# pecl_sampler_v3.net
KiCad netlist of a schematic drawn in EAGLE
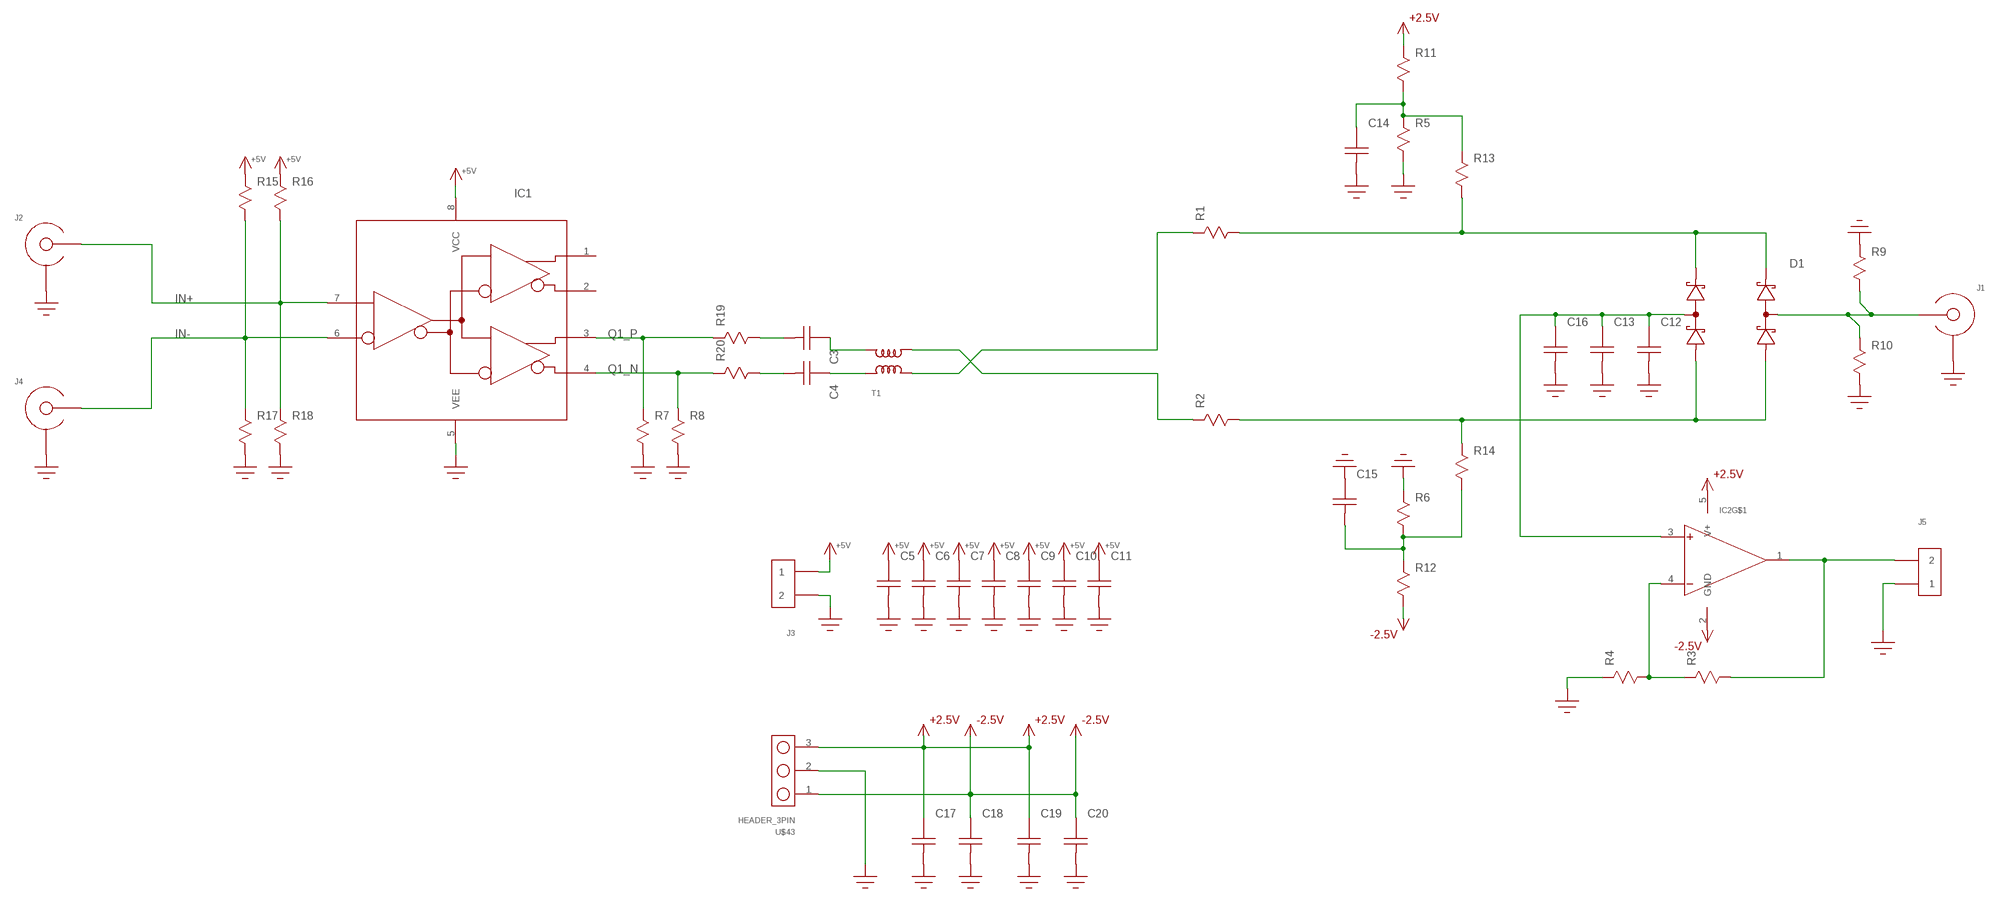
[diagram p0: schematic, sheet 1]

(export (version "E")
  (design (tool "Eeschema 10.0.6"))
  (components
    (comp (ref "C3") (value "C") (footprint "eagle-import:C0402") (libsource (lib "eagle-import") (part "C")))
    (comp (ref "C4") (value "C") (footprint "eagle-import:C0402") (libsource (lib "eagle-import") (part "C")))
    (comp (ref "C5")
      (value "C0603")
      (footprint "eagle-import:C0603")
      (libsource (lib "eagle-import") (part "C0603"))
    )
    (comp (ref "C6")
      (value "C0603")
      (footprint "eagle-import:C0603")
      (libsource (lib "eagle-import") (part "C0603"))
    )
    (comp (ref "C7")
      (value "C0805")
      (footprint "eagle-import:0805")
      (libsource (lib "eagle-import") (part "C0805"))
    )
    (comp (ref "C8")
      (value "C0603")
      (footprint "eagle-import:C0603")
      (libsource (lib "eagle-import") (part "C0603"))
    )
    (comp (ref "C9")
      (value "C0603")
      (footprint "eagle-import:C0603")
      (libsource (lib "eagle-import") (part "C0603"))
    )
    (comp (ref "C10")
      (value "C0603")
      (footprint "eagle-import:C0603")
      (libsource (lib "eagle-import") (part "C0603"))
    )
    (comp (ref "C11")
      (value "C0603")
      (footprint "eagle-import:C0603")
      (libsource (lib "eagle-import") (part "C0603"))
    )
    (comp (ref "C12")
      (value "C")
      (footprint "eagle-import:C0402")
      (libsource (lib "eagle-import") (part "C"))
    )
    (comp (ref "C13")
      (value "C")
      (footprint "eagle-import:C0402")
      (libsource (lib "eagle-import") (part "C"))
    )
    (comp (ref "C14")
      (value "C")
      (footprint "eagle-import:C0402")
      (libsource (lib "eagle-import") (part "C"))
    )
    (comp (ref "C15")
      (value "C")
      (footprint "eagle-import:C0402")
      (libsource (lib "eagle-import") (part "C"))
    )
    (comp (ref "C16")
      (value "C")
      (footprint "eagle-import:C0402")
      (libsource (lib "eagle-import") (part "C"))
    )
    (comp (ref "C17")
      (value "C0603")
      (footprint "eagle-import:C0603")
      (libsource (lib "eagle-import") (part "C0603"))
    )
    (comp (ref "C18")
      (value "C0603")
      (footprint "eagle-import:C0603")
      (libsource (lib "eagle-import") (part "C0603"))
    )
    (comp (ref "C19")
      (value "C0603")
      (footprint "eagle-import:C0603")
      (libsource (lib "eagle-import") (part "C0603"))
    )
    (comp (ref "C20")
      (value "C0603")
      (footprint "eagle-import:C0603")
      (libsource (lib "eagle-import") (part "C0603"))
    )
    (comp (ref "D1")
      (value "SMS3923-081")
      (footprint "eagle-import:SC-88")
      (libsource (lib "eagle-import") (part "SMS3923-081"))
    )
    (comp (ref "IC1")
      (value "SY10EP89V")
      (footprint "eagle-import:SOIC8")
      (libsource (lib "eagle-import") (part "SY10EP89V"))
    )
    (comp (ref "IC2")
      (value "MCP6V81")
      (footprint "eagle-import:SOT23-5")
      (libsource (lib "eagle-import") (part "MCP6V81"))
    )
    (comp (ref "J1")
      (value "SMA-EDGE-LAUNCH4L-4020-TAPER-FIXED")
      (footprint "eagle-import:SMA_EDGE_LAUNCH_4L_4020_TAPER_FIXED")
      (libsource (lib "eagle-import") (part "SMA-EDGE-LAUNCH4L-4020-TAPER-FIXED"))
    )
    (comp (ref "J2")
      (value "SMA-EDGE-LAUNCH4L-4020-TAPER-FIXED")
      (footprint "eagle-import:SMA_EDGE_LAUNCH_4L_4020_TAPER_FIXED")
      (libsource (lib "eagle-import") (part "SMA-EDGE-LAUNCH4L-4020-TAPER-FIXED"))
    )
    (comp (ref "J3")
      (value "HEADER_2PIN")
      (footprint "eagle-import:HEADER_2PIN")
      (libsource (lib "eagle-import") (part "HEADER_2PIN"))
    )
    (comp (ref "J4")
      (value "SMA-EDGE-LAUNCH4L-4020-TAPER-FIXED")
      (footprint "eagle-import:SMA_EDGE_LAUNCH_4L_4020_TAPER_FIXED")
      (libsource (lib "eagle-import") (part "SMA-EDGE-LAUNCH4L-4020-TAPER-FIXED"))
    )
    (comp (ref "J5")
      (value "HEADER_2PIN")
      (footprint "eagle-import:HEADER_2PIN")
      (libsource (lib "eagle-import") (part "HEADER_2PIN"))
    )
    (comp (ref "R1")
      (value "R0402")
      (footprint "eagle-import:0402")
      (libsource (lib "eagle-import") (part "R0402"))
    )
    (comp (ref "R2")
      (value "R0402")
      (footprint "eagle-import:0402")
      (libsource (lib "eagle-import") (part "R0402"))
    )
    (comp (ref "R3")
      (value "R0603")
      (footprint "eagle-import:R0603")
      (libsource (lib "eagle-import") (part "R0603"))
    )
    (comp (ref "R4")
      (value "R0603")
      (footprint "eagle-import:R0603")
      (libsource (lib "eagle-import") (part "R0603"))
    )
    (comp (ref "R5")
      (value "R0603")
      (footprint "eagle-import:R0603")
      (libsource (lib "eagle-import") (part "R0603"))
    )
    (comp (ref "R6")
      (value "R0603")
      (footprint "eagle-import:R0603")
      (libsource (lib "eagle-import") (part "R0603"))
    )
    (comp (ref "R7")
      (value "R0603")
      (footprint "eagle-import:R0603")
      (libsource (lib "eagle-import") (part "R0603"))
    )
    (comp (ref "R8")
      (value "R0603")
      (footprint "eagle-import:R0603")
      (libsource (lib "eagle-import") (part "R0603"))
    )
    (comp (ref "R9")
      (value "R0402")
      (footprint "eagle-import:0402")
      (libsource (lib "eagle-import") (part "R0402"))
    )
    (comp (ref "R10")
      (value "R0402")
      (footprint "eagle-import:0402")
      (libsource (lib "eagle-import") (part "R0402"))
    )
    (comp (ref "R11")
      (value "R0603")
      (footprint "eagle-import:R0603")
      (libsource (lib "eagle-import") (part "R0603"))
    )
    (comp (ref "R12")
      (value "R0603")
      (footprint "eagle-import:R0603")
      (libsource (lib "eagle-import") (part "R0603"))
    )
    (comp (ref "R13")
      (value "R0402")
      (footprint "eagle-import:0402")
      (libsource (lib "eagle-import") (part "R0402"))
    )
    (comp (ref "R14")
      (value "R0402")
      (footprint "eagle-import:0402")
      (libsource (lib "eagle-import") (part "R0402"))
    )
    (comp (ref "R15")
      (value "R0603")
      (footprint "eagle-import:R0603")
      (libsource (lib "eagle-import") (part "R0603"))
    )
    (comp (ref "R16")
      (value "R0603")
      (footprint "eagle-import:R0603")
      (libsource (lib "eagle-import") (part "R0603"))
    )
    (comp (ref "R17")
      (value "R0603")
      (footprint "eagle-import:R0603")
      (libsource (lib "eagle-import") (part "R0603"))
    )
    (comp (ref "R18")
      (value "R0603")
      (footprint "eagle-import:R0603")
      (libsource (lib "eagle-import") (part "R0603"))
    )
    (comp (ref "R19")
      (value "R0402")
      (footprint "eagle-import:0402")
      (libsource (lib "eagle-import") (part "R0402"))
    )
    (comp (ref "R20")
      (value "R0402")
      (footprint "eagle-import:0402")
      (libsource (lib "eagle-import") (part "R0402"))
    )
    (comp (ref "T1")
      (value "MABA007159")
      (footprint "eagle-import:MABAES0061")
      (libsource (lib "eagle-import") (part "MABA007159"))
    )
    (comp (ref "U$43")
      (value "HEADER_3PIN")
      (footprint "eagle-import:HEADER_3PIN")
      (libsource (lib "eagle-import") (part "HEADER_3PIN"))
    )
  )
  (nets
    (net (code "1") (name "+2.5V") (class "Default")
      (node (ref "C17") (pin "P$2") (pinfunction "P$2_P$2") (pintype "bidirectional"))
      (node (ref "C19") (pin "P$2") (pinfunction "P$2_P$2") (pintype "bidirectional"))
      (node (ref "IC2") (pin "5") (pinfunction "V+_5") (pintype "bidirectional"))
      (node (ref "R11") (pin "P$1") (pinfunction "P$3_P$1") (pintype "bidirectional"))
      (node (ref "U$43") (pin "3") (pinfunction "3_3") (pintype "bidirectional"))
    )
    (net (code "2") (name "+5V") (class "Default")
      (node (ref "C10") (pin "P$2") (pinfunction "P$2_P$2") (pintype "bidirectional"))
      (node (ref "C11") (pin "P$2") (pinfunction "P$2_P$2") (pintype "bidirectional"))
      (node (ref "C5") (pin "P$2") (pinfunction "P$2_P$2") (pintype "bidirectional"))
      (node (ref "C6") (pin "P$2") (pinfunction "P$2_P$2") (pintype "bidirectional"))
      (node (ref "C7") (pin "P$2") (pinfunction "P$2_P$2") (pintype "bidirectional"))
      (node (ref "C8") (pin "P$2") (pinfunction "P$2_P$2") (pintype "bidirectional"))
      (node (ref "C9") (pin "P$2") (pinfunction "P$2_P$2") (pintype "bidirectional"))
      (node (ref "IC1") (pin "8") (pinfunction "VCC_8") (pintype "bidirectional"))
      (node (ref "J3") (pin "1") (pinfunction "1_1") (pintype "bidirectional"))
      (node (ref "R15") (pin "P$1") (pinfunction "P$3_P$1") (pintype "bidirectional"))
      (node (ref "R16") (pin "P$1") (pinfunction "P$3_P$1") (pintype "bidirectional"))
    )
    (net (code "3") (name "-2.5V") (class "Default")
      (node (ref "C18") (pin "P$2") (pinfunction "P$2_P$2") (pintype "bidirectional"))
      (node (ref "C20") (pin "P$2") (pinfunction "P$2_P$2") (pintype "bidirectional"))
      (node (ref "IC2") (pin "2") (pinfunction "GND_2") (pintype "bidirectional"))
      (node (ref "R12") (pin "P$2") (pinfunction "P$4_P$2") (pintype "bidirectional"))
      (node (ref "U$43") (pin "1") (pinfunction "1_1") (pintype "bidirectional"))
    )
    (net (code "4") (name "/IN+") (class "Default")
      (node (ref "IC1") (pin "7") (pinfunction "D_7") (pintype "bidirectional"))
      (node (ref "J2") (pin "CENTER@1") (pinfunction "CENTER_CENTER@1") (pintype "bidirectional"))
      (node (ref "J2") (pin "P$3") (pinfunction "CENTER_P$3") (pintype "bidirectional"))
      (node (ref "R16") (pin "P$2") (pinfunction "P$4_P$2") (pintype "bidirectional"))
      (node (ref "R18") (pin "P$1") (pinfunction "P$3_P$1") (pintype "bidirectional"))
    )
    (net (code "5") (name "/IN-") (class "Default")
      (node (ref "IC1") (pin "6") (pinfunction "~{D}_6") (pintype "bidirectional"))
      (node (ref "J4") (pin "CENTER@1") (pinfunction "CENTER_CENTER@1") (pintype "bidirectional"))
      (node (ref "J4") (pin "P$3") (pinfunction "CENTER_P$3") (pintype "bidirectional"))
      (node (ref "R15") (pin "P$2") (pinfunction "P$4_P$2") (pintype "bidirectional"))
      (node (ref "R17") (pin "P$1") (pinfunction "P$3_P$1") (pintype "bidirectional"))
    )
    (net (code "6") (name "/Q1_N") (class "Default")
      (node (ref "IC1") (pin "4") (pinfunction "~{Q1}_4") (pintype "bidirectional"))
      (node (ref "R20") (pin "1") (pinfunction "P$3_1") (pintype "bidirectional"))
      (node (ref "R8") (pin "P$1") (pinfunction "P$3_P$1") (pintype "bidirectional"))
    )
    (net (code "7") (name "/Q1_P") (class "Default")
      (node (ref "IC1") (pin "3") (pinfunction "Q1_3") (pintype "bidirectional"))
      (node (ref "R19") (pin "1") (pinfunction "P$3_1") (pintype "bidirectional"))
      (node (ref "R7") (pin "P$1") (pinfunction "P$3_P$1") (pintype "bidirectional"))
    )
    (net (code "8") (name "GND") (class "Default")
      (node (ref "C10") (pin "P$1") (pinfunction "P$1_P$1") (pintype "bidirectional"))
      (node (ref "C11") (pin "P$1") (pinfunction "P$1_P$1") (pintype "bidirectional"))
      (node (ref "C12") (pin "1") (pinfunction "P$1_1") (pintype "bidirectional"))
      (node (ref "C13") (pin "1") (pinfunction "P$1_1") (pintype "bidirectional"))
      (node (ref "C14") (pin "1") (pinfunction "P$1_1") (pintype "bidirectional"))
      (node (ref "C15") (pin "2") (pinfunction "P$2_2") (pintype "bidirectional"))
      (node (ref "C16") (pin "1") (pinfunction "P$1_1") (pintype "bidirectional"))
      (node (ref "C17") (pin "P$1") (pinfunction "P$1_P$1") (pintype "bidirectional"))
      (node (ref "C18") (pin "P$1") (pinfunction "P$1_P$1") (pintype "bidirectional"))
      (node (ref "C19") (pin "P$1") (pinfunction "P$1_P$1") (pintype "bidirectional"))
      (node (ref "C20") (pin "P$1") (pinfunction "P$1_P$1") (pintype "bidirectional"))
      (node (ref "C5") (pin "P$1") (pinfunction "P$1_P$1") (pintype "bidirectional"))
      (node (ref "C6") (pin "P$1") (pinfunction "P$1_P$1") (pintype "bidirectional"))
      (node (ref "C7") (pin "P$1") (pinfunction "P$1_P$1") (pintype "bidirectional"))
      (node (ref "C8") (pin "P$1") (pinfunction "P$1_P$1") (pintype "bidirectional"))
      (node (ref "C9") (pin "P$1") (pinfunction "P$1_P$1") (pintype "bidirectional"))
      (node (ref "IC1") (pin "5") (pinfunction "VEE_5") (pintype "bidirectional"))
      (node (ref "J1") (pin "BOTTOM_GND") (pinfunction "SHIELD_BOTTOM_GND") (pintype "bidirectional"))
      (node (ref "J1") (pin "GND@1") (pinfunction "SHIELD_GND@1") (pintype "bidirectional"))
      (node (ref "J1") (pin "GND@14") (pinfunction "SHIELD_GND@14") (pintype "bidirectional"))
      (node (ref "J1") (pin "GND@15") (pinfunction "SHIELD_GND@15") (pintype "bidirectional"))
      (node (ref "J1") (pin "GND@16") (pinfunction "SHIELD_GND@16") (pintype "bidirectional"))
      (node (ref "J1") (pin "GND@17") (pinfunction "SHIELD_GND@17") (pintype "bidirectional"))
      (node (ref "J1") (pin "GND@2") (pinfunction "SHIELD_GND@2") (pintype "bidirectional"))
      (node (ref "J1") (pin "GND@3") (pinfunction "SHIELD_GND@3") (pintype "bidirectional"))
      (node (ref "J1") (pin "GND@4") (pinfunction "SHIELD_GND@4") (pintype "bidirectional"))
      (node (ref "J1") (pin "GND@5") (pinfunction "SHIELD_GND@5") (pintype "bidirectional"))
      (node (ref "J1") (pin "GND@6") (pinfunction "SHIELD_GND@6") (pintype "bidirectional"))
      (node (ref "J1") (pin "GND@7") (pinfunction "SHIELD_GND@7") (pintype "bidirectional"))
      (node (ref "J1") (pin "GND@8") (pinfunction "SHIELD_GND@8") (pintype "bidirectional"))
      (node (ref "J1") (pin "GND_PAD1") (pinfunction "SHIELD_GND_PAD1") (pintype "bidirectional"))
      (node (ref "J1") (pin "GND_PAD2") (pinfunction "SHIELD_GND_PAD2") (pintype "bidirectional"))
      (node (ref "J1") (pin "P$1") (pinfunction "SHIELD_P$1") (pintype "bidirectional"))
      (node (ref "J1") (pin "P$2") (pinfunction "SHIELD_P$2") (pintype "bidirectional"))
      (node (ref "J2") (pin "BOTTOM_GND") (pinfunction "SHIELD_BOTTOM_GND") (pintype "bidirectional"))
      (node (ref "J2") (pin "GND@1") (pinfunction "SHIELD_GND@1") (pintype "bidirectional"))
      (node (ref "J2") (pin "GND@14") (pinfunction "SHIELD_GND@14") (pintype "bidirectional"))
      (node (ref "J2") (pin "GND@15") (pinfunction "SHIELD_GND@15") (pintype "bidirectional"))
      (node (ref "J2") (pin "GND@16") (pinfunction "SHIELD_GND@16") (pintype "bidirectional"))
      (node (ref "J2") (pin "GND@17") (pinfunction "SHIELD_GND@17") (pintype "bidirectional"))
      (node (ref "J2") (pin "GND@2") (pinfunction "SHIELD_GND@2") (pintype "bidirectional"))
      (node (ref "J2") (pin "GND@3") (pinfunction "SHIELD_GND@3") (pintype "bidirectional"))
      (node (ref "J2") (pin "GND@4") (pinfunction "SHIELD_GND@4") (pintype "bidirectional"))
      (node (ref "J2") (pin "GND@5") (pinfunction "SHIELD_GND@5") (pintype "bidirectional"))
      (node (ref "J2") (pin "GND@6") (pinfunction "SHIELD_GND@6") (pintype "bidirectional"))
      (node (ref "J2") (pin "GND@7") (pinfunction "SHIELD_GND@7") (pintype "bidirectional"))
      (node (ref "J2") (pin "GND@8") (pinfunction "SHIELD_GND@8") (pintype "bidirectional"))
      (node (ref "J2") (pin "GND_PAD1") (pinfunction "SHIELD_GND_PAD1") (pintype "bidirectional"))
      (node (ref "J2") (pin "GND_PAD2") (pinfunction "SHIELD_GND_PAD2") (pintype "bidirectional"))
      (node (ref "J2") (pin "P$1") (pinfunction "SHIELD_P$1") (pintype "bidirectional"))
      (node (ref "J2") (pin "P$2") (pinfunction "SHIELD_P$2") (pintype "bidirectional"))
      (node (ref "J3") (pin "2") (pinfunction "2_2") (pintype "bidirectional"))
      (node (ref "J4") (pin "BOTTOM_GND") (pinfunction "SHIELD_BOTTOM_GND") (pintype "bidirectional"))
      (node (ref "J4") (pin "GND@1") (pinfunction "SHIELD_GND@1") (pintype "bidirectional"))
      (node (ref "J4") (pin "GND@14") (pinfunction "SHIELD_GND@14") (pintype "bidirectional"))
      (node (ref "J4") (pin "GND@15") (pinfunction "SHIELD_GND@15") (pintype "bidirectional"))
      (node (ref "J4") (pin "GND@16") (pinfunction "SHIELD_GND@16") (pintype "bidirectional"))
      (node (ref "J4") (pin "GND@17") (pinfunction "SHIELD_GND@17") (pintype "bidirectional"))
      (node (ref "J4") (pin "GND@2") (pinfunction "SHIELD_GND@2") (pintype "bidirectional"))
      (node (ref "J4") (pin "GND@3") (pinfunction "SHIELD_GND@3") (pintype "bidirectional"))
      (node (ref "J4") (pin "GND@4") (pinfunction "SHIELD_GND@4") (pintype "bidirectional"))
      (node (ref "J4") (pin "GND@5") (pinfunction "SHIELD_GND@5") (pintype "bidirectional"))
      (node (ref "J4") (pin "GND@6") (pinfunction "SHIELD_GND@6") (pintype "bidirectional"))
      (node (ref "J4") (pin "GND@7") (pinfunction "SHIELD_GND@7") (pintype "bidirectional"))
      (node (ref "J4") (pin "GND@8") (pinfunction "SHIELD_GND@8") (pintype "bidirectional"))
      (node (ref "J4") (pin "GND_PAD1") (pinfunction "SHIELD_GND_PAD1") (pintype "bidirectional"))
      (node (ref "J4") (pin "GND_PAD2") (pinfunction "SHIELD_GND_PAD2") (pintype "bidirectional"))
      (node (ref "J4") (pin "P$1") (pinfunction "SHIELD_P$1") (pintype "bidirectional"))
      (node (ref "J4") (pin "P$2") (pinfunction "SHIELD_P$2") (pintype "bidirectional"))
      (node (ref "J5") (pin "1") (pinfunction "1_1") (pintype "bidirectional"))
      (node (ref "R10") (pin "2") (pinfunction "P$4_2") (pintype "bidirectional"))
      (node (ref "R17") (pin "P$2") (pinfunction "P$4_P$2") (pintype "bidirectional"))
      (node (ref "R18") (pin "P$2") (pinfunction "P$4_P$2") (pintype "bidirectional"))
      (node (ref "R4") (pin "P$1") (pinfunction "P$3_P$1") (pintype "bidirectional"))
      (node (ref "R5") (pin "P$2") (pinfunction "P$4_P$2") (pintype "bidirectional"))
      (node (ref "R6") (pin "P$1") (pinfunction "P$3_P$1") (pintype "bidirectional"))
      (node (ref "R7") (pin "P$2") (pinfunction "P$4_P$2") (pintype "bidirectional"))
      (node (ref "R8") (pin "P$2") (pinfunction "P$4_P$2") (pintype "bidirectional"))
      (node (ref "R9") (pin "1") (pinfunction "P$3_1") (pintype "bidirectional"))
      (node (ref "U$43") (pin "2") (pinfunction "2_2") (pintype "bidirectional"))
    )
    (net (code "9") (name "Net-(C3-P$1)") (class "Default")
      (node (ref "C3") (pin "1") (pinfunction "P$1_1") (pintype "bidirectional"))
      (node (ref "R19") (pin "2") (pinfunction "P$4_2") (pintype "bidirectional"))
    )
    (net (code "10") (name "Net-(C3-P$2)") (class "Default")
      (node (ref "C3") (pin "2") (pinfunction "P$2_2") (pintype "bidirectional"))
      (node (ref "T1") (pin "4") (pinfunction "4_4") (pintype "bidirectional"))
    )
    (net (code "11") (name "Net-(C4-P$1)") (class "Default")
      (node (ref "C4") (pin "1") (pinfunction "P$1_1") (pintype "bidirectional"))
      (node (ref "R20") (pin "2") (pinfunction "P$4_2") (pintype "bidirectional"))
    )
    (net (code "12") (name "Net-(C4-P$2)") (class "Default")
      (node (ref "C4") (pin "2") (pinfunction "P$2_2") (pintype "bidirectional"))
      (node (ref "T1") (pin "5") (pinfunction "5_5") (pintype "bidirectional"))
    )
    (net (code "13") (name "Net-(C12-P$2)") (class "Default")
      (node (ref "C12") (pin "2") (pinfunction "P$2_2") (pintype "bidirectional"))
      (node (ref "C13") (pin "2") (pinfunction "P$2_2") (pintype "bidirectional"))
      (node (ref "C16") (pin "2") (pinfunction "P$2_2") (pintype "bidirectional"))
      (node (ref "D1") (pin "5") (pinfunction "COMMON1_5") (pintype "bidirectional"))
      (node (ref "IC2") (pin "3") (pinfunction "+_3") (pintype "bidirectional"))
    )
    (net (code "14") (name "Net-(C14-P$2)") (class "Default")
      (node (ref "C14") (pin "2") (pinfunction "P$2_2") (pintype "bidirectional"))
      (node (ref "R11") (pin "P$2") (pinfunction "P$4_P$2") (pintype "bidirectional"))
      (node (ref "R13") (pin "1") (pinfunction "P$3_1") (pintype "bidirectional"))
      (node (ref "R5") (pin "P$1") (pinfunction "P$3_P$1") (pintype "bidirectional"))
    )
    (net (code "15") (name "Net-(C15-P$1)") (class "Default")
      (node (ref "C15") (pin "1") (pinfunction "P$1_1") (pintype "bidirectional"))
      (node (ref "R12") (pin "P$1") (pinfunction "P$3_P$1") (pintype "bidirectional"))
      (node (ref "R14") (pin "2") (pinfunction "P$4_2") (pintype "bidirectional"))
      (node (ref "R6") (pin "P$2") (pinfunction "P$4_P$2") (pintype "bidirectional"))
    )
    (net (code "16") (name "Net-(D1-ANODE0)") (class "Default")
      (node (ref "D1") (pin "1") (pinfunction "ANODE0_1") (pintype "bidirectional"))
      (node (ref "D1") (pin "6") (pinfunction "ANODE1_6") (pintype "bidirectional"))
      (node (ref "R14") (pin "1") (pinfunction "P$3_1") (pintype "bidirectional"))
      (node (ref "R2") (pin "2") (pinfunction "P$4_2") (pintype "bidirectional"))
    )
    (net (code "17") (name "Net-(D1-CATHODE0)") (class "Default")
      (node (ref "D1") (pin "3") (pinfunction "CATHODE0_3") (pintype "bidirectional"))
      (node (ref "D1") (pin "4") (pinfunction "CATHODE1_4") (pintype "bidirectional"))
      (node (ref "R1") (pin "2") (pinfunction "P$4_2") (pintype "bidirectional"))
      (node (ref "R13") (pin "2") (pinfunction "P$4_2") (pintype "bidirectional"))
    )
    (net (code "18") (name "Net-(D1-COMMON0)") (class "Default")
      (node (ref "D1") (pin "2") (pinfunction "COMMON0_2") (pintype "bidirectional"))
      (node (ref "J1") (pin "CENTER@1") (pinfunction "CENTER_CENTER@1") (pintype "bidirectional"))
      (node (ref "J1") (pin "P$3") (pinfunction "CENTER_P$3") (pintype "bidirectional"))
      (node (ref "R10") (pin "1") (pinfunction "P$3_1") (pintype "bidirectional"))
      (node (ref "R9") (pin "2") (pinfunction "P$4_2") (pintype "bidirectional"))
    )
    (net (code "19") (name "Net-(IC2A--)") (class "Default")
      (node (ref "IC2") (pin "4") (pinfunction "-_4") (pintype "bidirectional"))
      (node (ref "R3") (pin "P$1") (pinfunction "P$3_P$1") (pintype "bidirectional"))
      (node (ref "R4") (pin "P$2") (pinfunction "P$4_P$2") (pintype "bidirectional"))
    )
    (net (code "20") (name "Net-(IC2A-OUT)") (class "Default")
      (node (ref "IC2") (pin "1") (pinfunction "OUT_1") (pintype "bidirectional"))
      (node (ref "J5") (pin "2") (pinfunction "2_2") (pintype "bidirectional"))
      (node (ref "R3") (pin "P$2") (pinfunction "P$4_P$2") (pintype "bidirectional"))
    )
    (net (code "21") (name "Net-(R1-P$3)") (class "Default")
      (node (ref "R1") (pin "1") (pinfunction "P$3_1") (pintype "bidirectional"))
      (node (ref "T1") (pin "1") (pinfunction "1_1") (pintype "bidirectional"))
    )
    (net (code "22") (name "Net-(R2-P$3)") (class "Default")
      (node (ref "R2") (pin "1") (pinfunction "P$3_1") (pintype "bidirectional"))
      (node (ref "T1") (pin "3") (pinfunction "3_3") (pintype "bidirectional"))
    )
    (net (code "23") (name "unconnected-(IC1-Q0-Pad1)") (class "Default")
      (node (ref "IC1") (pin "1") (pinfunction "Q0_1") (pintype "bidirectional"))
    )
    (net (code "24") (name "unconnected-(IC1-~{Q0}-Pad2)") (class "Default")
      (node (ref "IC1") (pin "2") (pinfunction "~{Q0}_2") (pintype "bidirectional"))
    )
  )
)
